# hkk_project.net
KiCad netlist of a schematic drawn in EAGLE
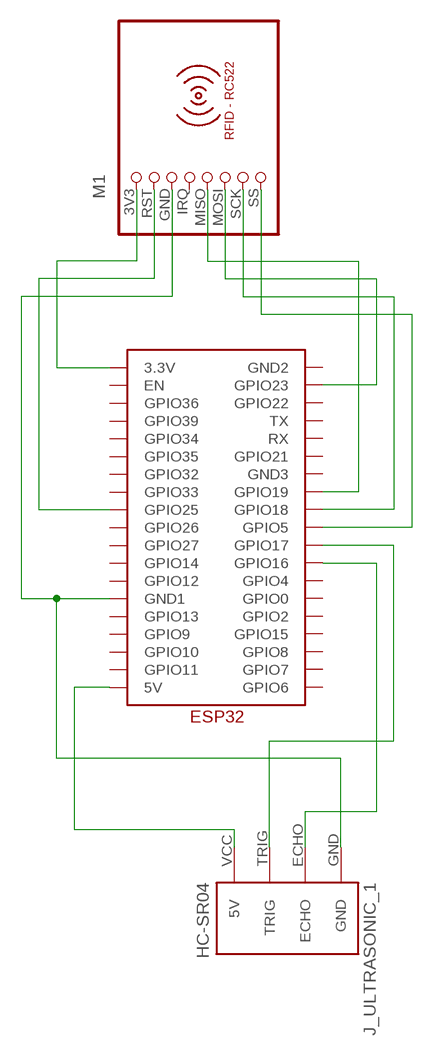
[diagram p0: schematic, sheet 1]

(export (version "E")
  (design (tool "Eeschema 10.0.6"))
  (components
    (comp (ref "J_ULTRASONIC_1")
      (value "HC-SR04")
      (footprint "eagle-import:HC-SR04_FOOTPRINT")
      (libsource (lib "eagle-import") (part "HC-SR04"))
    )
    (comp (ref "M1")
      (value "RFID-RC522")
      (footprint "eagle-import:RFID-RC522")
      (libsource (lib "eagle-import") (part "RFID-RC522"))
    )
    (comp (ref "U$1")
      (value "ESP32_GRBL")
      (footprint "eagle-import:ESP32_GRBL")
      (libsource (lib "eagle-import") (part "ESP32_GRBL"))
    )
  )
  (nets
    (net (code "1") (name "Net-(J_ULTRASONIC_1-5V)") (class "Default")
      (node (ref "J_ULTRASONIC_1") (pin "VCC") (pinfunction "5V_VCC") (pintype "bidirectional"))
      (node (ref "U$1") (pin "5V") (pinfunction "5V_5V") (pintype "bidirectional"))
    )
    (net (code "2") (name "Net-(J_ULTRASONIC_1-PadECHO)") (class "Default")
      (node (ref "J_ULTRASONIC_1") (pin "ECHO") (pinfunction "ECHO_ECHO") (pintype "bidirectional"))
      (node (ref "U$1") (pin "GPIO16") (pinfunction "GPIO16_GPIO16") (pintype "bidirectional"))
    )
    (net (code "3") (name "Net-(J_ULTRASONIC_1-PadTRIG)") (class "Default")
      (node (ref "J_ULTRASONIC_1") (pin "TRIG") (pinfunction "TRIG_TRIG") (pintype "bidirectional"))
      (node (ref "U$1") (pin "GPIO17") (pinfunction "GPIO17_GPIO17") (pintype "bidirectional"))
    )
    (net (code "4") (name "Net-(M1-1)") (class "Default")
      (node (ref "M1") (pin "3V3") (pinfunction "1_3V3") (pintype "passive"))
      (node (ref "U$1") (pin "3.3V") (pinfunction "3.3V_3.3V") (pintype "bidirectional"))
    )
    (net (code "5") (name "Net-(M1-2)") (class "Default")
      (node (ref "M1") (pin "RST") (pinfunction "2_RST") (pintype "passive"))
      (node (ref "U$1") (pin "GPIO25") (pinfunction "GPIO25_GPIO25") (pintype "bidirectional"))
    )
    (net (code "6") (name "Net-(M1-3)") (class "Default")
      (node (ref "J_ULTRASONIC_1") (pin "GND") (pinfunction "GND_GND") (pintype "bidirectional"))
      (node (ref "M1") (pin "GND") (pinfunction "3_GND") (pintype "passive"))
      (node (ref "U$1") (pin "GND1") (pinfunction "GND1_GND1") (pintype "bidirectional"))
    )
    (net (code "7") (name "Net-(M1-5)") (class "Default")
      (node (ref "M1") (pin "MISO") (pinfunction "5_MISO") (pintype "passive"))
      (node (ref "U$1") (pin "GPIO19") (pinfunction "GPIO19_GPIO19") (pintype "bidirectional"))
    )
    (net (code "8") (name "Net-(M1-6)") (class "Default")
      (node (ref "M1") (pin "MOSI") (pinfunction "6_MOSI") (pintype "passive"))
      (node (ref "U$1") (pin "GPIO23") (pinfunction "GPIO23_GPIO23") (pintype "bidirectional"))
    )
    (net (code "9") (name "Net-(M1-7)") (class "Default")
      (node (ref "M1") (pin "SCK") (pinfunction "7_SCK") (pintype "passive"))
      (node (ref "U$1") (pin "GPIO18") (pinfunction "GPIO18_GPIO18") (pintype "bidirectional"))
    )
    (net (code "10") (name "Net-(M1-8)") (class "Default")
      (node (ref "M1") (pin "SS") (pinfunction "8_SS") (pintype "passive"))
      (node (ref "U$1") (pin "GPIO5") (pinfunction "GPIO5_GPIO5") (pintype "bidirectional"))
    )
    (net (code "11") (name "unconnected-(M1-4-PadIRQ)") (class "Default")
      (node (ref "M1") (pin "IRQ") (pinfunction "4_IRQ") (pintype "passive"))
    )
    (net (code "12") (name "unconnected-(U$1-PadEN)") (class "Default")
      (node (ref "U$1") (pin "EN") (pinfunction "EN_EN") (pintype "bidirectional"))
    )
    (net (code "13") (name "unconnected-(U$1-PadGND2)") (class "Default")
      (node (ref "U$1") (pin "GND2") (pinfunction "GND2_GND2") (pintype "bidirectional"))
    )
    (net (code "14") (name "unconnected-(U$1-PadGND3)") (class "Default")
      (node (ref "U$1") (pin "GND3") (pinfunction "GND3_GND3") (pintype "bidirectional"))
    )
    (net (code "15") (name "unconnected-(U$1-PadGPIO0)") (class "Default")
      (node (ref "U$1") (pin "GPIO0") (pinfunction "GPIO0_GPIO0") (pintype "bidirectional"))
    )
    (net (code "16") (name "unconnected-(U$1-PadGPIO2)") (class "Default")
      (node (ref "U$1") (pin "GPIO2") (pinfunction "GPIO2_GPIO2") (pintype "bidirectional"))
    )
    (net (code "17") (name "unconnected-(U$1-PadGPIO4)") (class "Default")
      (node (ref "U$1") (pin "GPIO4") (pinfunction "GPIO4_GPIO4") (pintype "bidirectional"))
    )
    (net (code "18") (name "unconnected-(U$1-PadGPIO6)") (class "Default")
      (node (ref "U$1") (pin "GPIO6") (pinfunction "GPIO6_GPIO6") (pintype "bidirectional"))
    )
    (net (code "19") (name "unconnected-(U$1-PadGPIO7)") (class "Default")
      (node (ref "U$1") (pin "GPIO7") (pinfunction "GPIO7_GPIO7") (pintype "bidirectional"))
    )
    (net (code "20") (name "unconnected-(U$1-PadGPIO8)") (class "Default")
      (node (ref "U$1") (pin "GPIO8") (pinfunction "GPIO8_GPIO8") (pintype "bidirectional"))
    )
    (net (code "21") (name "unconnected-(U$1-PadGPIO9)") (class "Default")
      (node (ref "U$1") (pin "GPIO9") (pinfunction "GPIO9_GPIO9") (pintype "bidirectional"))
    )
    (net (code "22") (name "unconnected-(U$1-PadGPIO10)") (class "Default")
      (node (ref "U$1") (pin "GPIO10") (pinfunction "GPIO10_GPIO10") (pintype "bidirectional"))
    )
    (net (code "23") (name "unconnected-(U$1-PadGPIO11)") (class "Default")
      (node (ref "U$1") (pin "GPIO11") (pinfunction "GPIO11_GPIO11") (pintype "bidirectional"))
    )
    (net (code "24") (name "unconnected-(U$1-PadGPIO12)") (class "Default")
      (node (ref "U$1") (pin "GPIO12") (pinfunction "GPIO12_GPIO12") (pintype "bidirectional"))
    )
    (net (code "25") (name "unconnected-(U$1-PadGPIO13)") (class "Default")
      (node (ref "U$1") (pin "GPIO13") (pinfunction "GPIO13_GPIO13") (pintype "bidirectional"))
    )
    (net (code "26") (name "unconnected-(U$1-PadGPIO14)") (class "Default")
      (node (ref "U$1") (pin "GPIO14") (pinfunction "GPIO14_GPIO14") (pintype "bidirectional"))
    )
    (net (code "27") (name "unconnected-(U$1-PadGPIO15)") (class "Default")
      (node (ref "U$1") (pin "GPIO15") (pinfunction "GPIO15_GPIO15") (pintype "bidirectional"))
    )
    (net (code "28") (name "unconnected-(U$1-PadGPIO21)") (class "Default")
      (node (ref "U$1") (pin "GPIO21") (pinfunction "GPIO21_GPIO21") (pintype "bidirectional"))
    )
    (net (code "29") (name "unconnected-(U$1-PadGPIO22)") (class "Default")
      (node (ref "U$1") (pin "GPIO22") (pinfunction "GPIO22_GPIO22") (pintype "bidirectional"))
    )
    (net (code "30") (name "unconnected-(U$1-PadGPIO26)") (class "Default")
      (node (ref "U$1") (pin "GPIO26") (pinfunction "GPIO26_GPIO26") (pintype "bidirectional"))
    )
    (net (code "31") (name "unconnected-(U$1-PadGPIO27)") (class "Default")
      (node (ref "U$1") (pin "GPIO27") (pinfunction "GPIO27_GPIO27") (pintype "bidirectional"))
    )
    (net (code "32") (name "unconnected-(U$1-PadGPIO32)") (class "Default")
      (node (ref "U$1") (pin "GPIO32") (pinfunction "GPIO32_GPIO32") (pintype "bidirectional"))
    )
    (net (code "33") (name "unconnected-(U$1-PadGPIO33)") (class "Default")
      (node (ref "U$1") (pin "GPIO33") (pinfunction "GPIO33_GPIO33") (pintype "bidirectional"))
    )
    (net (code "34") (name "unconnected-(U$1-PadGPIO34)") (class "Default")
      (node (ref "U$1") (pin "GPIO34") (pinfunction "GPIO34_GPIO34") (pintype "bidirectional"))
    )
    (net (code "35") (name "unconnected-(U$1-PadGPIO35)") (class "Default")
      (node (ref "U$1") (pin "GPIO35") (pinfunction "GPIO35_GPIO35") (pintype "bidirectional"))
    )
    (net (code "36") (name "unconnected-(U$1-PadGPIO36)") (class "Default")
      (node (ref "U$1") (pin "GPIO36") (pinfunction "GPIO36_GPIO36") (pintype "bidirectional"))
    )
    (net (code "37") (name "unconnected-(U$1-PadGPIO39)") (class "Default")
      (node (ref "U$1") (pin "GPIO39") (pinfunction "GPIO39_GPIO39") (pintype "bidirectional"))
    )
    (net (code "38") (name "unconnected-(U$1-PadRX)") (class "Default")
      (node (ref "U$1") (pin "RX") (pinfunction "RX_RX") (pintype "bidirectional"))
    )
    (net (code "39") (name "unconnected-(U$1-PadTX)") (class "Default")
      (node (ref "U$1") (pin "TX") (pinfunction "TX_TX") (pintype "bidirectional"))
    )
  )
)
